# STM_and_connectors.net
KiCad netlist of a schematic drawn in Altium Designer
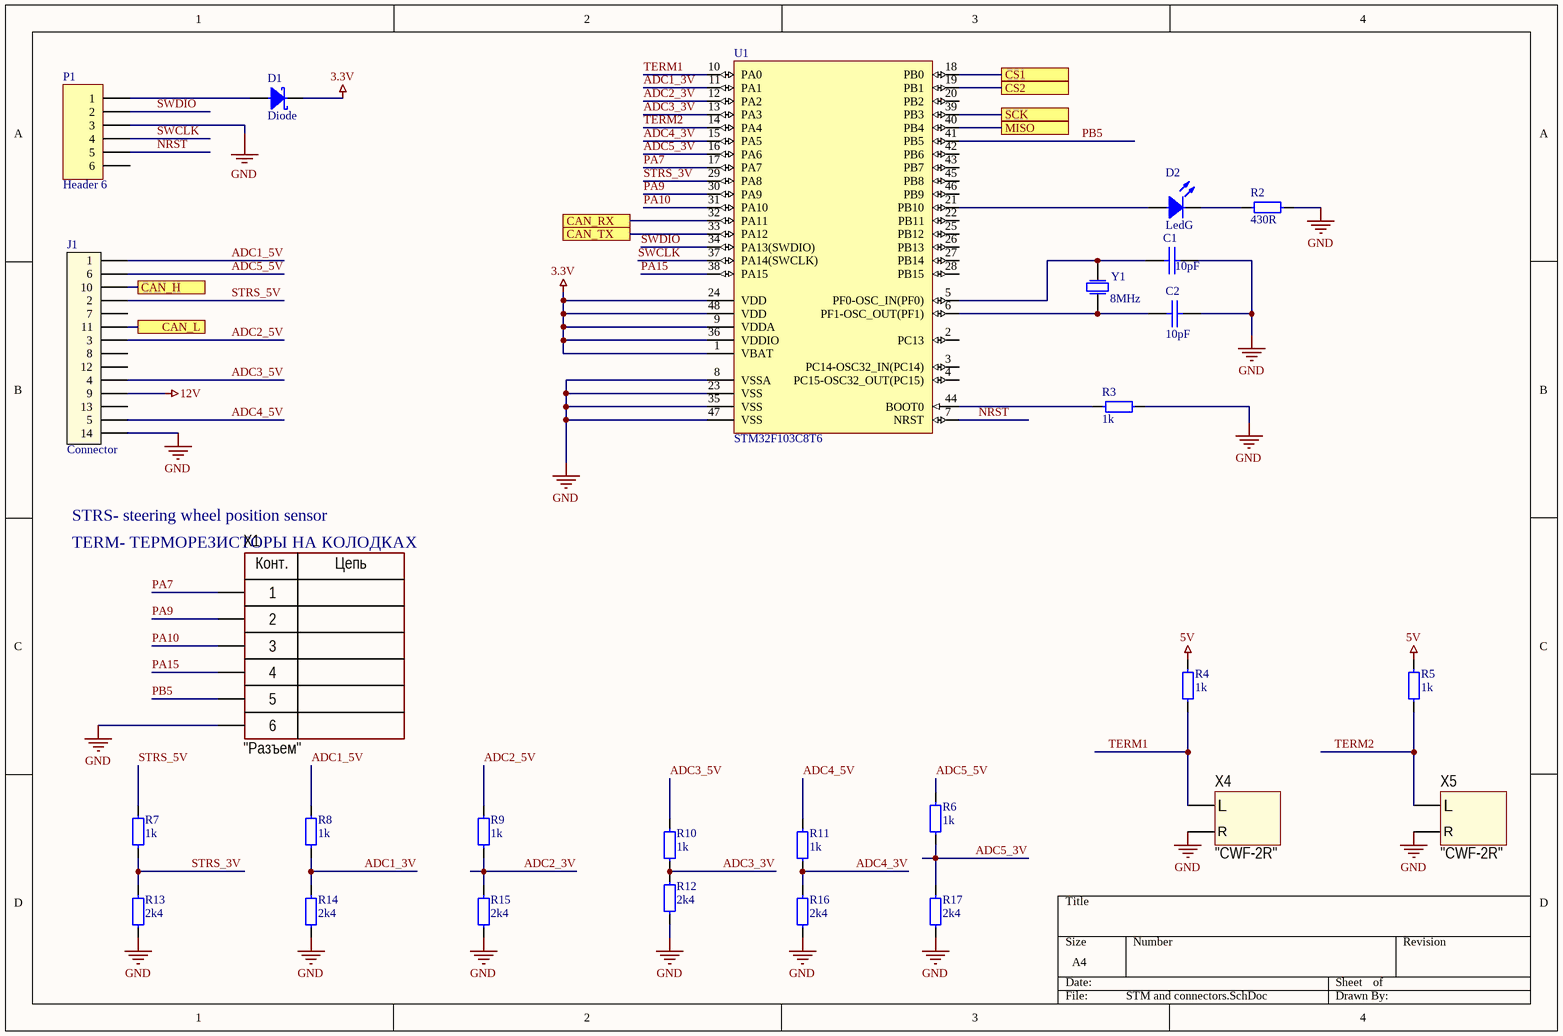
[diagram p0: STM and connectors.SchDoc]

(export (version "E")
  (design (tool "Eeschema 10.0.6"))
  (components
    (comp (ref "C1")
      (value "10pF")
      (footprint "0805 Capicator")
      (description "10pF NP0 50V 5% 0805")
      (fields
        (field (name "MANUFACTURER") "Murata Manufacturing")
        (field (name "PART NUMBER") "GRM2165C1H100JZ01D")
      )
      (libsource (lib "BRT_Components") (part "Cap 10pF (0805)"))
    )
    (comp (ref "C2")
      (value "10pF")
      (footprint "0805 Capicator")
      (description "10pF NP0 50V 5% 0805")
      (fields
        (field (name "MANUFACTURER") "Murata Manufacturing")
        (field (name "PART NUMBER") "GRM2165C1H100JZ01D")
      )
      (libsource (lib "BRT_Components") (part "Cap 10pF (0805)"))
    )
    (comp (ref "D1")
      (value "Diode")
      (footprint "SMA")
      (description "Diode Schottky 3A 40V")
      (fields (field (name "PART NUMBER") "B340A-E3/61T") (field (name "MANUFACTURER") "Vishay"))
      (libsource (lib "BRT_Components") (part "Diode Schottky (SMA)"))
    )
    (comp (ref "D2")
      (value "LedG")
      (footprint "0805 LED")
      (description "Led Green SMD 1608, 120°, 525nM")
      (fields
        (field (name "PART NUMBER") "TO-1608BC-PG")
        (field (name "MANUFACTURER") "Taiwan Oasis Technology")
      )
      (libsource (lib "BRT_Components") (part "Led Green"))
    )
    (comp (ref "J1")
      (value "Connector")
      (footprint "AMP 776266-1")
      (description "AMP Connector")
      (fields (field (name "PART NUMBER") "776266-1") (field (name "MANUFACTURER") "TE Connectivity"))
      (libsource (lib "BRT_Components") (part "Connector AMP"))
    )
    (comp (ref "P1")
      (value "Header 6")
      (footprint "HDR1X6")
      (description "Header, 6-Pin")
      (fields (field (name "PUBLISHER") "Altium Limited"))
      (libsource (lib "Miscellaneous Connectors") (part "Header 6"))
    )
    (comp (ref "R2")
      (value "430R")
      (footprint "0805 Resistor")
      (description "0.125W 0805 430R, 1%")
      (fields (field (name "PART NUMBER") "RC0805FR-07430RL") (field (name "MANUFACTURER") "Taiwan"))
      (libsource (lib "BRT_Components") (part "Res 430R (0805)"))
    )
    (comp (ref "R3")
      (value "1k")
      (footprint "0805 Resistor")
      (description "0.125W 0805 1k, 1%")
      (fields (field (name "PART NUMBER") "RC0805FR-071KL") (field (name "MANUFACTURER") "Taiwan"))
      (libsource (lib "BRT_Components") (part "Res 1k (0805)"))
    )
    (comp (ref "R4")
      (value "1k")
      (footprint "0805 Resistor")
      (description "0.125W 0805 1k, 1%")
      (fields (field (name "PART NUMBER") "RC0805FR-071KL") (field (name "MANUFACTURER") "Taiwan"))
      (libsource (lib "BRT_Components") (part "Res 1k (0805)"))
    )
    (comp (ref "R5")
      (value "1k")
      (footprint "0805 Resistor")
      (description "0.125W 0805 1k, 1%")
      (fields (field (name "PART NUMBER") "RC0805FR-071KL") (field (name "MANUFACTURER") "Taiwan"))
      (libsource (lib "BRT_Components") (part "Res 1k (0805)"))
    )
    (comp (ref "R6")
      (value "1k")
      (footprint "0805 Resistor")
      (description "0.125W 0805 1k, 1%")
      (fields (field (name "PART NUMBER") "RC0805FR-071KL") (field (name "MANUFACTURER") "Taiwan"))
      (libsource (lib "BRT_Components") (part "Res 1k (0805)"))
    )
    (comp (ref "R7")
      (value "1k")
      (footprint "0805 Resistor")
      (description "0.125W 0805 1k, 1%")
      (fields (field (name "PART NUMBER") "RC0805FR-071KL") (field (name "MANUFACTURER") "Taiwan"))
      (libsource (lib "BRT_Components") (part "Res 1k (0805)"))
    )
    (comp (ref "R8")
      (value "1k")
      (footprint "0805 Resistor")
      (description "0.125W 0805 1k, 1%")
      (fields (field (name "PART NUMBER") "RC0805FR-071KL") (field (name "MANUFACTURER") "Taiwan"))
      (libsource (lib "BRT_Components") (part "Res 1k (0805)"))
    )
    (comp (ref "R9")
      (value "1k")
      (footprint "0805 Resistor")
      (description "0.125W 0805 1k, 1%")
      (fields (field (name "PART NUMBER") "RC0805FR-071KL") (field (name "MANUFACTURER") "Taiwan"))
      (libsource (lib "BRT_Components") (part "Res 1k (0805)"))
    )
    (comp (ref "R10")
      (value "1k")
      (footprint "0805 Resistor")
      (description "0.125W 0805 1k, 1%")
      (fields (field (name "PART NUMBER") "RC0805FR-071KL") (field (name "MANUFACTURER") "Taiwan"))
      (libsource (lib "BRT_Components") (part "Res 1k (0805)"))
    )
    (comp (ref "R11")
      (value "1k")
      (footprint "0805 Resistor")
      (description "0.125W 0805 1k, 1%")
      (fields (field (name "PART NUMBER") "RC0805FR-071KL") (field (name "MANUFACTURER") "Taiwan"))
      (libsource (lib "BRT_Components") (part "Res 1k (0805)"))
    )
    (comp (ref "R12")
      (value "2k4")
      (footprint "0805 Resistor")
      (description "0.125W 0805 2.4k, 1%")
      (fields (field (name "PART NUMBER") "RC0805FR-072K4L") (field (name "MANUFACTURER") "Taiwan"))
      (libsource (lib "BRT_Components") (part "Res 2.4k (0805)"))
    )
    (comp (ref "R13")
      (value "2k4")
      (footprint "0805 Resistor")
      (description "0.125W 0805 2.4k, 1%")
      (fields (field (name "PART NUMBER") "RC0805FR-072K4L") (field (name "MANUFACTURER") "Taiwan"))
      (libsource (lib "BRT_Components") (part "Res 2.4k (0805)"))
    )
    (comp (ref "R14")
      (value "2k4")
      (footprint "0805 Resistor")
      (description "0.125W 0805 2.4k, 1%")
      (fields (field (name "PART NUMBER") "RC0805FR-072K4L") (field (name "MANUFACTURER") "Taiwan"))
      (libsource (lib "BRT_Components") (part "Res 2.4k (0805)"))
    )
    (comp (ref "R15")
      (value "2k4")
      (footprint "0805 Resistor")
      (description "0.125W 0805 2.4k, 1%")
      (fields (field (name "PART NUMBER") "RC0805FR-072K4L") (field (name "MANUFACTURER") "Taiwan"))
      (libsource (lib "BRT_Components") (part "Res 2.4k (0805)"))
    )
    (comp (ref "R16")
      (value "2k4")
      (footprint "0805 Resistor")
      (description "0.125W 0805 2.4k, 1%")
      (fields (field (name "PART NUMBER") "RC0805FR-072K4L") (field (name "MANUFACTURER") "Taiwan"))
      (libsource (lib "BRT_Components") (part "Res 2.4k (0805)"))
    )
    (comp (ref "R17")
      (value "2k4")
      (footprint "0805 Resistor")
      (description "0.125W 0805 2.4k, 1%")
      (fields (field (name "PART NUMBER") "RC0805FR-072K4L") (field (name "MANUFACTURER") "Taiwan"))
      (libsource (lib "BRT_Components") (part "Res 2.4k (0805)"))
    )
    (comp (ref "U1")
      (value "STM32F103C8T6")
      (footprint "LQFP48")
      (description "Cortex™-M3 32-bit RISC core operating at a 72 MHz frequency")
      (fields (field (name "MANUFACTURER") "STMicroelectronics"))
      (libsource (lib "BRT_Components") (part "STM32F103C8T6"))
    )
    (comp (ref "X1")
      (value "~")
      (footprint "CON: PLD-6")
      (fields
        (field (name "MANUFACTURER") "Connfly")
        (field (name "VALUEMANUFACTURERPARTNUMBER") "Connector, 6pin, 2.54mm, 500VAC, 3A")
        (field (name "PARTNUMBER") "PLD-6")
        (field (name "COMMENTTEXT") "\"Разъем\"")
      )
      (libsource (lib "Connector") (part "PLD-6"))
    )
    (comp (ref "X4")
      (value "~")
      (footprint "CON: CWF-2R")
      (fields
        (field (name "MANUFACTURER") "Connfly")
        (field (name "VALUEMANUFACTURERPARTNUMBER") "Connector, 2pin, 2.54mm, 250VAC, 3A")
        (field (name "PARTNUMBER") "CWF-2R")
        (field (name "COMMENTTEXT") "\"CWF-2R\"")
      )
      (libsource (lib "Connector") (part "CWF-2R"))
    )
    (comp (ref "X5")
      (value "~")
      (footprint "CON: CWF-2R")
      (fields
        (field (name "MANUFACTURER") "Connfly")
        (field (name "VALUEMANUFACTURERPARTNUMBER") "Connector, 2pin, 2.54mm, 250VAC, 3A")
        (field (name "PARTNUMBER") "CWF-2R")
        (field (name "COMMENTTEXT") "\"CWF-2R\"")
      )
      (libsource (lib "Connector") (part "CWF-2R"))
    )
    (comp (ref "Y1")
      (value "8MHz")
      (footprint "R38")
      (description "Crystal. HC-49S (US)")
      (fields (field (name "MANUFACTURER") "China") (field (name "PART NUMBER") "8.000MHzHC-49US"))
      (libsource (lib "BRT_Components") (part "Crystal 8MHz"))
    )
  )
  (nets
    (net (code "1") (name "/ADC1_3V") (class "Default")
      (node (ref "R14") (pin "1") (pinfunction "1_1") (pintype "passive"))
      (node (ref "R8") (pin "1") (pinfunction "1_1") (pintype "passive"))
      (node (ref "U1") (pin "11") (pinfunction "PA1_11") (pintype "bidirectional"))
    )
    (net (code "2") (name "/ADC1_5V") (class "Default")
      (node (ref "J1") (pin "1") (pinfunction "1_1") (pintype "passive"))
      (node (ref "R8") (pin "2") (pinfunction "2_2") (pintype "passive"))
    )
    (net (code "3") (name "/ADC2_3V") (class "Default")
      (node (ref "R15") (pin "1") (pinfunction "1_1") (pintype "passive"))
      (node (ref "R9") (pin "1") (pinfunction "1_1") (pintype "passive"))
      (node (ref "U1") (pin "12") (pinfunction "PA2_12") (pintype "bidirectional"))
    )
    (net (code "4") (name "/ADC2_5V") (class "Default")
      (node (ref "J1") (pin "3") (pinfunction "3_3") (pintype "passive"))
      (node (ref "R9") (pin "2") (pinfunction "2_2") (pintype "passive"))
    )
    (net (code "5") (name "/ADC3_3V") (class "Default")
      (node (ref "R10") (pin "1") (pinfunction "1_1") (pintype "passive"))
      (node (ref "R12") (pin "1") (pinfunction "1_1") (pintype "passive"))
      (node (ref "U1") (pin "13") (pinfunction "PA3_13") (pintype "bidirectional"))
    )
    (net (code "6") (name "/ADC3_5V") (class "Default")
      (node (ref "J1") (pin "4") (pinfunction "4_4") (pintype "passive"))
      (node (ref "R10") (pin "2") (pinfunction "2_2") (pintype "passive"))
    )
    (net (code "7") (name "/ADC4_3V") (class "Default")
      (node (ref "R11") (pin "1") (pinfunction "1_1") (pintype "passive"))
      (node (ref "R16") (pin "1") (pinfunction "1_1") (pintype "passive"))
      (node (ref "U1") (pin "15") (pinfunction "PA5_15") (pintype "bidirectional"))
    )
    (net (code "8") (name "/ADC4_5V") (class "Default")
      (node (ref "J1") (pin "5") (pinfunction "5_5") (pintype "passive"))
      (node (ref "R11") (pin "2") (pinfunction "2_2") (pintype "passive"))
    )
    (net (code "9") (name "/ADC5_3V") (class "Default")
      (node (ref "R17") (pin "1") (pinfunction "1_1") (pintype "passive"))
      (node (ref "R6") (pin "1") (pinfunction "1_1") (pintype "passive"))
      (node (ref "U1") (pin "16") (pinfunction "PA6_16") (pintype "bidirectional"))
    )
    (net (code "10") (name "/ADC5_5V") (class "Default")
      (node (ref "J1") (pin "6") (pinfunction "6_6") (pintype "passive"))
      (node (ref "R6") (pin "2") (pinfunction "2_2") (pintype "passive"))
    )
    (net (code "11") (name "/CAN_H") (class "Default")
      (node (ref "J1") (pin "10") (pinfunction "10_10") (pintype "passive"))
    )
    (net (code "12") (name "/CAN_L") (class "Default")
      (node (ref "J1") (pin "11") (pinfunction "11_11") (pintype "passive"))
    )
    (net (code "13") (name "/CAN_RX") (class "Default")
      (node (ref "U1") (pin "32") (pinfunction "PA11_32") (pintype "bidirectional"))
    )
    (net (code "14") (name "/CAN_TX") (class "Default")
      (node (ref "U1") (pin "33") (pinfunction "PA12_33") (pintype "bidirectional"))
    )
    (net (code "15") (name "/CS1") (class "Default")
      (node (ref "U1") (pin "18") (pinfunction "PB0_18") (pintype "bidirectional"))
    )
    (net (code "16") (name "/CS2") (class "Default")
      (node (ref "U1") (pin "19") (pinfunction "PB1_19") (pintype "bidirectional"))
    )
    (net (code "17") (name "/MISO") (class "Default")
      (node (ref "U1") (pin "40") (pinfunction "PB4_40") (pintype "bidirectional"))
    )
    (net (code "18") (name "/NRST") (class "Default")
      (node (ref "P1") (pin "5") (pinfunction "5_5") (pintype "passive"))
      (node (ref "U1") (pin "7") (pinfunction "NRST_7") (pintype "bidirectional"))
    )
    (net (code "19") (name "/PA7") (class "Default")
      (node (ref "U1") (pin "17") (pinfunction "PA7_17") (pintype "bidirectional"))
      (node (ref "X1") (pin "1") (pinfunction "1_1") (pintype "passive"))
    )
    (net (code "20") (name "/PA9") (class "Default")
      (node (ref "U1") (pin "30") (pinfunction "PA9_30") (pintype "bidirectional"))
      (node (ref "X1") (pin "2") (pinfunction "2_2") (pintype "passive"))
    )
    (net (code "21") (name "/PA10") (class "Default")
      (node (ref "U1") (pin "31") (pinfunction "PA10_31") (pintype "bidirectional"))
      (node (ref "X1") (pin "3") (pinfunction "3_3") (pintype "power_in"))
    )
    (net (code "22") (name "/PA15") (class "Default")
      (node (ref "U1") (pin "38") (pinfunction "PA15_38") (pintype "bidirectional"))
      (node (ref "X1") (pin "4") (pinfunction "4_4") (pintype "power_in"))
    )
    (net (code "23") (name "/PB5") (class "Default")
      (node (ref "U1") (pin "41") (pinfunction "PB5_41") (pintype "bidirectional"))
      (node (ref "X1") (pin "5") (pinfunction "5_5") (pintype "power_in"))
    )
    (net (code "24") (name "/SCK") (class "Default")
      (node (ref "U1") (pin "39") (pinfunction "PB3_39") (pintype "bidirectional"))
    )
    (net (code "25") (name "/STRS_3V") (class "Default")
      (node (ref "R13") (pin "1") (pinfunction "1_1") (pintype "passive"))
      (node (ref "R7") (pin "1") (pinfunction "1_1") (pintype "passive"))
      (node (ref "U1") (pin "29") (pinfunction "PA8_29") (pintype "bidirectional"))
    )
    (net (code "26") (name "/STRS_5V") (class "Default")
      (node (ref "J1") (pin "2") (pinfunction "2_2") (pintype "passive"))
      (node (ref "R7") (pin "2") (pinfunction "2_2") (pintype "passive"))
    )
    (net (code "27") (name "/SWCLK") (class "Default")
      (node (ref "P1") (pin "4") (pinfunction "4_4") (pintype "passive"))
      (node (ref "U1") (pin "37") (pinfunction "PA14(SWCLK)_37") (pintype "bidirectional"))
    )
    (net (code "28") (name "/SWDIO") (class "Default")
      (node (ref "P1") (pin "2") (pinfunction "2_2") (pintype "passive"))
      (node (ref "U1") (pin "34") (pinfunction "PA13(SWDIO)_34") (pintype "bidirectional"))
    )
    (net (code "29") (name "/TERM1") (class "Default")
      (node (ref "R4") (pin "1") (pinfunction "1_1") (pintype "passive"))
      (node (ref "U1") (pin "10") (pinfunction "PA0_10") (pintype "bidirectional"))
      (node (ref "X4") (pin "1") (pinfunction "L_1") (pintype "passive"))
    )
    (net (code "30") (name "/TERM2") (class "Default")
      (node (ref "R5") (pin "1") (pinfunction "1_1") (pintype "passive"))
      (node (ref "U1") (pin "14") (pinfunction "PA4_14") (pintype "bidirectional"))
      (node (ref "X5") (pin "1") (pinfunction "L_1") (pintype "passive"))
    )
    (net (code "31") (name "3.3V") (class "Default")
      (node (ref "D1") (pin "2") (pinfunction "2_2") (pintype "passive"))
      (node (ref "U1") (pin "1") (pinfunction "VBAT_1") (pintype "power_in"))
      (node (ref "U1") (pin "24") (pinfunction "VDD_24") (pintype "power_in"))
      (node (ref "U1") (pin "36") (pinfunction "VDDIO_36") (pintype "power_in"))
      (node (ref "U1") (pin "48") (pinfunction "VDD_48") (pintype "power_in"))
      (node (ref "U1") (pin "9") (pinfunction "VDDA_9") (pintype "power_in"))
    )
    (net (code "32") (name "5V") (class "Default")
      (node (ref "R4") (pin "2") (pinfunction "2_2") (pintype "passive"))
      (node (ref "R5") (pin "2") (pinfunction "2_2") (pintype "passive"))
    )
    (net (code "33") (name "12V") (class "Default")
      (node (ref "J1") (pin "9") (pinfunction "9_9") (pintype "passive"))
    )
    (net (code "34") (name "GND") (class "Default")
      (node (ref "C1") (pin "2") (pinfunction "2_2") (pintype "passive"))
      (node (ref "C2") (pin "2") (pinfunction "2_2") (pintype "passive"))
      (node (ref "J1") (pin "14") (pinfunction "14_14") (pintype "passive"))
      (node (ref "P1") (pin "3") (pinfunction "3_3") (pintype "passive"))
      (node (ref "R12") (pin "2") (pinfunction "2_2") (pintype "passive"))
      (node (ref "R13") (pin "2") (pinfunction "2_2") (pintype "passive"))
      (node (ref "R14") (pin "2") (pinfunction "2_2") (pintype "passive"))
      (node (ref "R15") (pin "2") (pinfunction "2_2") (pintype "passive"))
      (node (ref "R16") (pin "2") (pinfunction "2_2") (pintype "passive"))
      (node (ref "R17") (pin "2") (pinfunction "2_2") (pintype "passive"))
      (node (ref "R2") (pin "2") (pinfunction "2_2") (pintype "passive"))
      (node (ref "R3") (pin "2") (pinfunction "2_2") (pintype "passive"))
      (node (ref "U1") (pin "23") (pinfunction "VSS_23") (pintype "power_in"))
      (node (ref "U1") (pin "35") (pinfunction "VSS_35") (pintype "power_in"))
      (node (ref "U1") (pin "47") (pinfunction "VSS_47") (pintype "power_in"))
      (node (ref "U1") (pin "8") (pinfunction "VSSA_8") (pintype "power_in"))
      (node (ref "X1") (pin "6") (pinfunction "6_6") (pintype "power_in"))
      (node (ref "X4") (pin "2") (pinfunction "R_2") (pintype "passive"))
      (node (ref "X5") (pin "2") (pinfunction "R_2") (pintype "passive"))
    )
    (net (code "35") (name "Net-(D1-Pad1)") (class "Default")
      (node (ref "D1") (pin "1") (pinfunction "1_1") (pintype "passive"))
      (node (ref "P1") (pin "1") (pinfunction "1_1") (pintype "passive"))
    )
    (net (code "36") (name "Net-(D2-Pad2)") (class "Default")
      (node (ref "D2") (pin "2") (pinfunction "2_2") (pintype "passive"))
      (node (ref "R2") (pin "1") (pinfunction "1_1") (pintype "passive"))
    )
    (net (code "37") (name "Net-(U1-BOOT0)") (class "Default")
      (node (ref "R3") (pin "1") (pinfunction "1_1") (pintype "passive"))
      (node (ref "U1") (pin "44") (pinfunction "BOOT0_44") (pintype "input"))
    )
    (net (code "38") (name "Net-(U1-PB10)") (class "Default")
      (node (ref "D2") (pin "1") (pinfunction "1_1") (pintype "passive"))
      (node (ref "U1") (pin "21") (pinfunction "PB10_21") (pintype "bidirectional"))
    )
    (net (code "39") (name "Net-(U1-PF0-OSC_IN(PF0))") (class "Default")
      (node (ref "C1") (pin "1") (pinfunction "1_1") (pintype "passive"))
      (node (ref "U1") (pin "5") (pinfunction "PF0-OSC_IN(PF0)_5") (pintype "bidirectional"))
      (node (ref "Y1") (pin "2") (pinfunction "2_2") (pintype "passive"))
    )
    (net (code "40") (name "Net-(U1-PF1-OSC_OUT(PF1))") (class "Default")
      (node (ref "C2") (pin "1") (pinfunction "1_1") (pintype "passive"))
      (node (ref "U1") (pin "6") (pinfunction "PF1-OSC_OUT(PF1)_6") (pintype "bidirectional"))
      (node (ref "Y1") (pin "1") (pinfunction "1_1") (pintype "passive"))
    )
    (net (code "41") (name "unconnected-(J1-Pad7)") (class "Default")
      (node (ref "J1") (pin "7") (pinfunction "7_7") (pintype "passive"))
    )
    (net (code "42") (name "unconnected-(J1-Pad8)") (class "Default")
      (node (ref "J1") (pin "8") (pinfunction "8_8") (pintype "passive"))
    )
    (net (code "43") (name "unconnected-(J1-Pad12)") (class "Default")
      (node (ref "J1") (pin "12") (pinfunction "12_12") (pintype "passive"))
    )
    (net (code "44") (name "unconnected-(J1-Pad13)") (class "Default")
      (node (ref "J1") (pin "13") (pinfunction "13_13") (pintype "passive"))
    )
    (net (code "45") (name "unconnected-(P1-Pad6)") (class "Default")
      (node (ref "P1") (pin "6") (pinfunction "6_6") (pintype "passive"))
    )
    (net (code "46") (name "unconnected-(U1-PB2-Pad20)") (class "Default")
      (node (ref "U1") (pin "20") (pinfunction "PB2_20") (pintype "bidirectional"))
    )
    (net (code "47") (name "unconnected-(U1-PB6-Pad42)") (class "Default")
      (node (ref "U1") (pin "42") (pinfunction "PB6_42") (pintype "bidirectional"))
    )
    (net (code "48") (name "unconnected-(U1-PB7-Pad43)") (class "Default")
      (node (ref "U1") (pin "43") (pinfunction "PB7_43") (pintype "bidirectional"))
    )
    (net (code "49") (name "unconnected-(U1-PB8-Pad45)") (class "Default")
      (node (ref "U1") (pin "45") (pinfunction "PB8_45") (pintype "bidirectional"))
    )
    (net (code "50") (name "unconnected-(U1-PB9-Pad46)") (class "Default")
      (node (ref "U1") (pin "46") (pinfunction "PB9_46") (pintype "bidirectional"))
    )
    (net (code "51") (name "unconnected-(U1-PB11-Pad22)") (class "Default")
      (node (ref "U1") (pin "22") (pinfunction "PB11_22") (pintype "bidirectional"))
    )
    (net (code "52") (name "unconnected-(U1-PB12-Pad25)") (class "Default")
      (node (ref "U1") (pin "25") (pinfunction "PB12_25") (pintype "bidirectional"))
    )
    (net (code "53") (name "unconnected-(U1-PB13-Pad26)") (class "Default")
      (node (ref "U1") (pin "26") (pinfunction "PB13_26") (pintype "bidirectional"))
    )
    (net (code "54") (name "unconnected-(U1-PB14-Pad27)") (class "Default")
      (node (ref "U1") (pin "27") (pinfunction "PB14_27") (pintype "bidirectional"))
    )
    (net (code "55") (name "unconnected-(U1-PB15-Pad28)") (class "Default")
      (node (ref "U1") (pin "28") (pinfunction "PB15_28") (pintype "bidirectional"))
    )
    (net (code "56") (name "unconnected-(U1-PC13-Pad2)") (class "Default")
      (node (ref "U1") (pin "2") (pinfunction "PC13_2") (pintype "bidirectional"))
    )
    (net (code "57") (name "unconnected-(U1-PC14-OSC32_IN(PC14)-Pad3)") (class "Default")
      (node (ref "U1") (pin "3") (pinfunction "PC14-OSC32_IN(PC14)_3") (pintype "bidirectional"))
    )
    (net (code "58") (name "unconnected-(U1-PC15-OSC32_OUT(PC15)-Pad4)") (class "Default")
      (node (ref "U1") (pin "4") (pinfunction "PC15-OSC32_OUT(PC15)_4") (pintype "bidirectional"))
    )
  )
)
